# 5vSwitcher.net
KiCad netlist of a schematic drawn in EAGLE
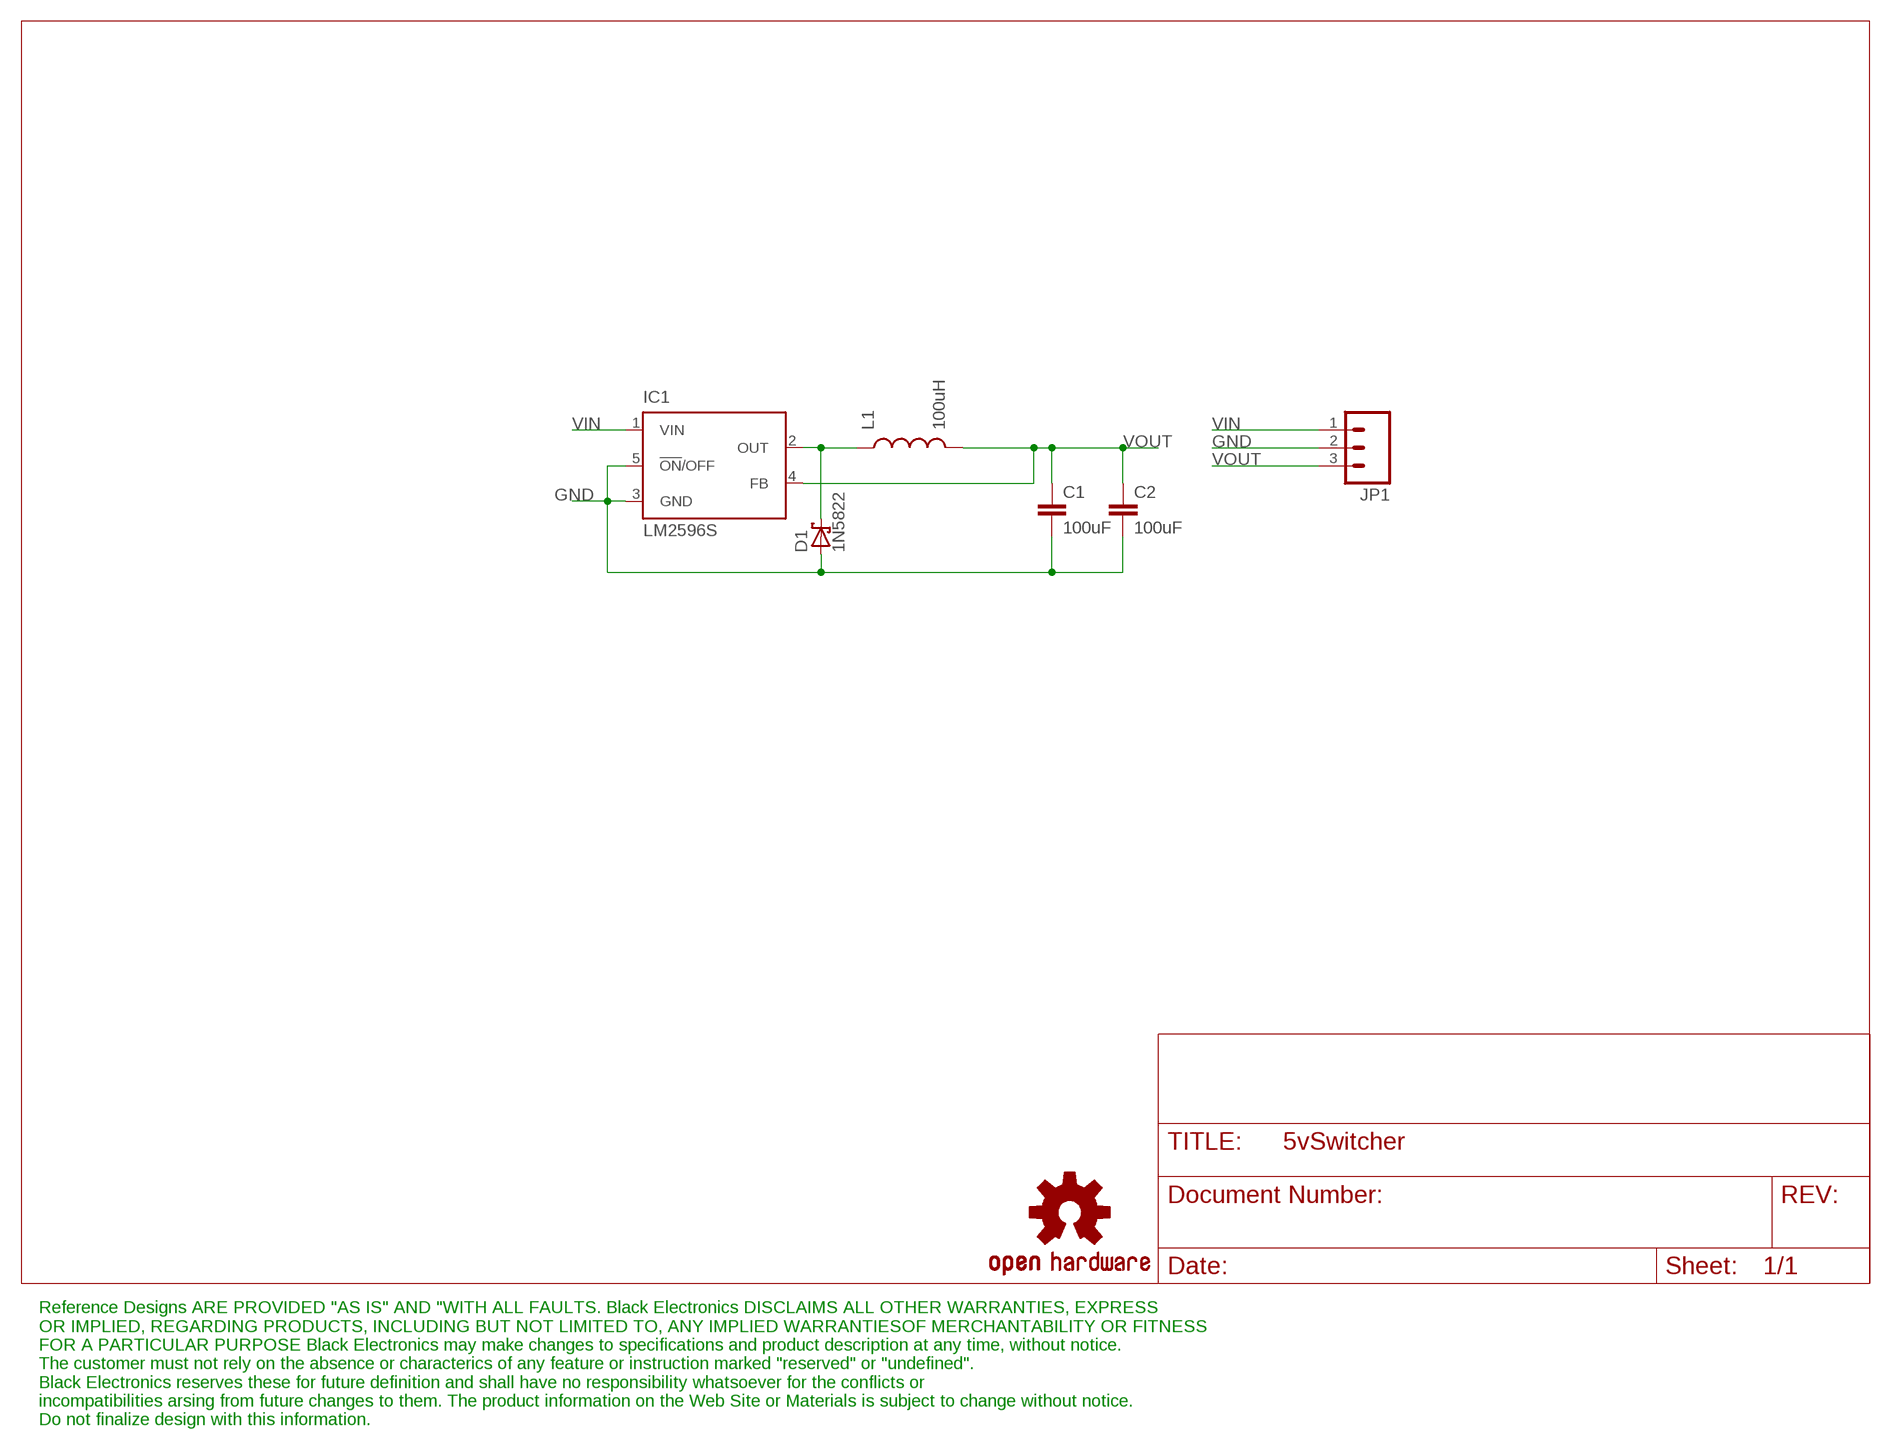
[diagram p0: schematic, sheet 1]

(export (version "E")
  (design (tool "Eeschema 10.0.6"))
  (components
    (comp (ref "C1")
      (value "100uF")
      (footprint "eagle-import:0805")
      (libsource (lib "eagle-import") (part "CAP0805"))
    )
    (comp (ref "C2")
      (value "100uF")
      (footprint "eagle-import:0805")
      (libsource (lib "eagle-import") (part "CAP0805"))
    )
    (comp (ref "D1")
      (value "1N5822")
      (footprint "eagle-import:SMC")
      (libsource (lib "eagle-import") (part "SCHOTTKY-DIODESMC"))
    )
    (comp (ref "IC1")
      (value "LM2596S")
      (footprint "eagle-import:TO263-5")
      (fields (field (name "MF") "NATIONAL SEMICONDUCTOR") (field (name "MPN") "LM2596S-ADJ/NOPB"))
      (libsource (lib "eagle-import") (part "LM2596S"))
    )
    (comp (ref "JP1")
      (value "M03PTH")
      (footprint "eagle-import:1X03")
      (libsource (lib "eagle-import") (part "M03PTH"))
    )
    (comp (ref "L1")
      (value "100uH")
      (footprint "eagle-import:INDUCTOR-1206")
      (libsource (lib "eagle-import") (part "INDUCTORH1206"))
    )
    (comp (ref "U$1")
      (value "OSHW-LOGOS")
      (footprint "eagle-import:OSHW-LOGO-S")
      (libsource (lib "eagle-import") (part "OSHW-LOGOS"))
    )
  )
  (nets
    (net (code "1") (name "/GND") (class "Default")
      (node (ref "C1") (pin "2") (pinfunction "2_2") (pintype "passive"))
      (node (ref "C2") (pin "2") (pinfunction "2_2") (pintype "passive"))
      (node (ref "D1") (pin "A") (pinfunction "A_A") (pintype "passive"))
      (node (ref "IC1") (pin "3") (pinfunction "GND_3") (pintype "power_in"))
      (node (ref "IC1") (pin "5") (pinfunction "~{ON}/OFF_5") (pintype "input"))
      (node (ref "JP1") (pin "2") (pinfunction "2_2") (pintype "passive"))
    )
    (net (code "2") (name "/VIN") (class "Default")
      (node (ref "IC1") (pin "1") (pinfunction "VIN_1") (pintype "input"))
      (node (ref "JP1") (pin "1") (pinfunction "1_1") (pintype "passive"))
    )
    (net (code "3") (name "/VOUT") (class "Default")
      (node (ref "C1") (pin "1") (pinfunction "1_1") (pintype "passive"))
      (node (ref "C2") (pin "1") (pinfunction "1_1") (pintype "passive"))
      (node (ref "IC1") (pin "4") (pinfunction "FB_4") (pintype "input"))
      (node (ref "JP1") (pin "3") (pinfunction "3_3") (pintype "passive"))
      (node (ref "L1") (pin "P$2") (pinfunction "2_P$2") (pintype "passive"))
    )
    (net (code "4") (name "Net-(IC1-OUT)") (class "Default")
      (node (ref "D1") (pin "C") (pinfunction "C_C") (pintype "passive"))
      (node (ref "IC1") (pin "2") (pinfunction "OUT_2") (pintype "output"))
      (node (ref "L1") (pin "P$1") (pinfunction "1_P$1") (pintype "passive"))
    )
  )
)
